# sister-board-SCHEMATIC.net
KiCad netlist of a schematic drawn in Altium Designer
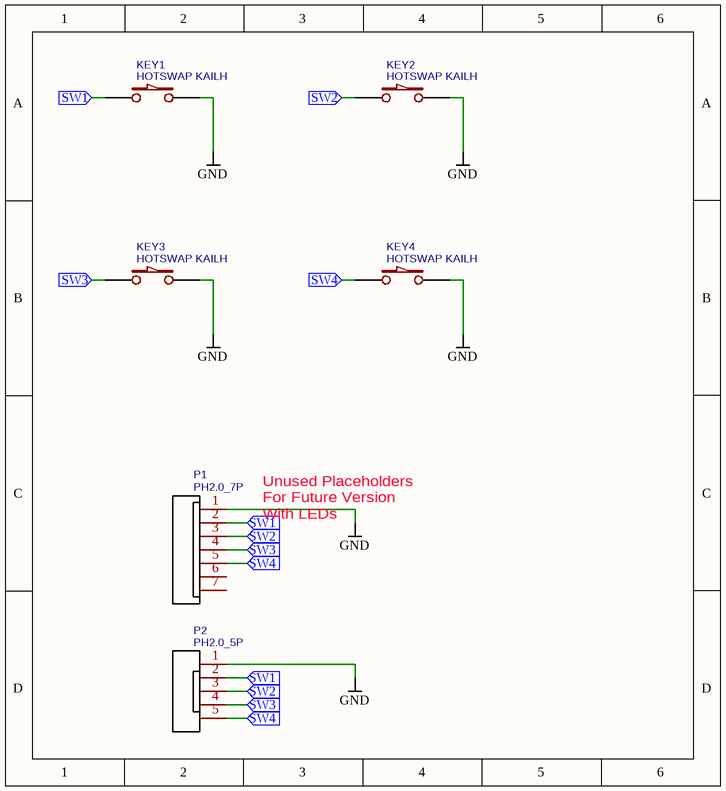
[diagram p0: sister-board-SCHEMATIC.schdoc]

(export (version "E")
  (design (tool "Eeschema 10.0.6"))
  (components
    (comp (ref "KEY1")
      (value "HOTSWAP KAILH")
      (fields
        (field (name "MANUFACTURER") "ReliaPro")
        (field (name "MANUFACTURER PART") "Switch3x4x2")
        (field (name "CONTRIBUTOR") "James Nixon")
      )
      (libsource (lib "altium-import") (part "root_0_HOTSWAP KAILH_"))
    )
    (comp (ref "KEY2")
      (value "HOTSWAP KAILH")
      (fields
        (field (name "MANUFACTURER") "ReliaPro")
        (field (name "MANUFACTURER PART") "Switch3x4x2")
        (field (name "CONTRIBUTOR") "James Nixon")
      )
      (libsource (lib "altium-import") (part "root_0_HOTSWAP KAILH_"))
    )
    (comp (ref "KEY3")
      (value "HOTSWAP KAILH")
      (fields
        (field (name "MANUFACTURER") "ReliaPro")
        (field (name "MANUFACTURER PART") "Switch3x4x2")
        (field (name "CONTRIBUTOR") "James Nixon")
      )
      (libsource (lib "altium-import") (part "root_0_HOTSWAP KAILH_"))
    )
    (comp (ref "KEY4")
      (value "HOTSWAP KAILH")
      (fields
        (field (name "MANUFACTURER") "ReliaPro")
        (field (name "MANUFACTURER PART") "Switch3x4x2")
        (field (name "CONTRIBUTOR") "James Nixon")
      )
      (libsource (lib "altium-import") (part "root_0_HOTSWAP KAILH_"))
    )
    (comp (ref "P1")
      (value "PH2.0_7P")
      (fields (field (name "MANUFACTURER PART") "New SchematicLib") (field (name "CONTRIBUTOR") "robellado"))
      (libsource (lib "altium-import") (part "root_0_PH2.0_7P_"))
    )
    (comp (ref "P2")
      (value "PH2.0_5P")
      (fields
        (field (name "MANUFACTURER PART") "New SchematicLib")
        (field (name "CONTRIBUTOR") "oleg.evsegneev")
      )
      (libsource (lib "altium-import") (part "root_0_PH2.0_5P_"))
    )
  )
  (nets
    (net (code "1") (name "/SW1") (class "Default")
      (node (ref "KEY1") (pin "1") (pinfunction "1_1") (pintype "passive"))
      (node (ref "P1") (pin "2") (pinfunction "2_2") (pintype "passive"))
      (node (ref "P2") (pin "2") (pinfunction "2_2") (pintype "passive"))
    )
    (net (code "2") (name "/SW2") (class "Default")
      (node (ref "KEY2") (pin "1") (pinfunction "1_1") (pintype "passive"))
      (node (ref "P1") (pin "3") (pinfunction "3_3") (pintype "passive"))
      (node (ref "P2") (pin "3") (pinfunction "3_3") (pintype "passive"))
    )
    (net (code "3") (name "/SW3") (class "Default")
      (node (ref "KEY3") (pin "1") (pinfunction "1_1") (pintype "passive"))
      (node (ref "P1") (pin "4") (pinfunction "4_4") (pintype "passive"))
      (node (ref "P2") (pin "4") (pinfunction "4_4") (pintype "passive"))
    )
    (net (code "4") (name "/SW4") (class "Default")
      (node (ref "KEY4") (pin "1") (pinfunction "1_1") (pintype "passive"))
      (node (ref "P1") (pin "5") (pinfunction "5_5") (pintype "passive"))
      (node (ref "P2") (pin "5") (pinfunction "5_5") (pintype "passive"))
    )
    (net (code "5") (name "GND") (class "Default")
      (node (ref "KEY1") (pin "2") (pinfunction "2_2") (pintype "passive"))
      (node (ref "KEY2") (pin "2") (pinfunction "2_2") (pintype "passive"))
      (node (ref "KEY3") (pin "2") (pinfunction "2_2") (pintype "passive"))
      (node (ref "KEY4") (pin "2") (pinfunction "2_2") (pintype "passive"))
      (node (ref "P1") (pin "1") (pinfunction "1_1") (pintype "passive"))
      (node (ref "P2") (pin "1") (pinfunction "1_1") (pintype "passive"))
    )
    (net (code "6") (name "unconnected-(P1-Pad6)") (class "Default")
      (node (ref "P1") (pin "6") (pinfunction "6_6") (pintype "passive"))
    )
    (net (code "7") (name "unconnected-(P1-Pad7)") (class "Default")
      (node (ref "P1") (pin "7") (pinfunction "7_7") (pintype "passive"))
    )
  )
)
